# ETH10M100_RJ45wMAGNET.net
KiCad netlist of a schematic drawn in Altium Designer
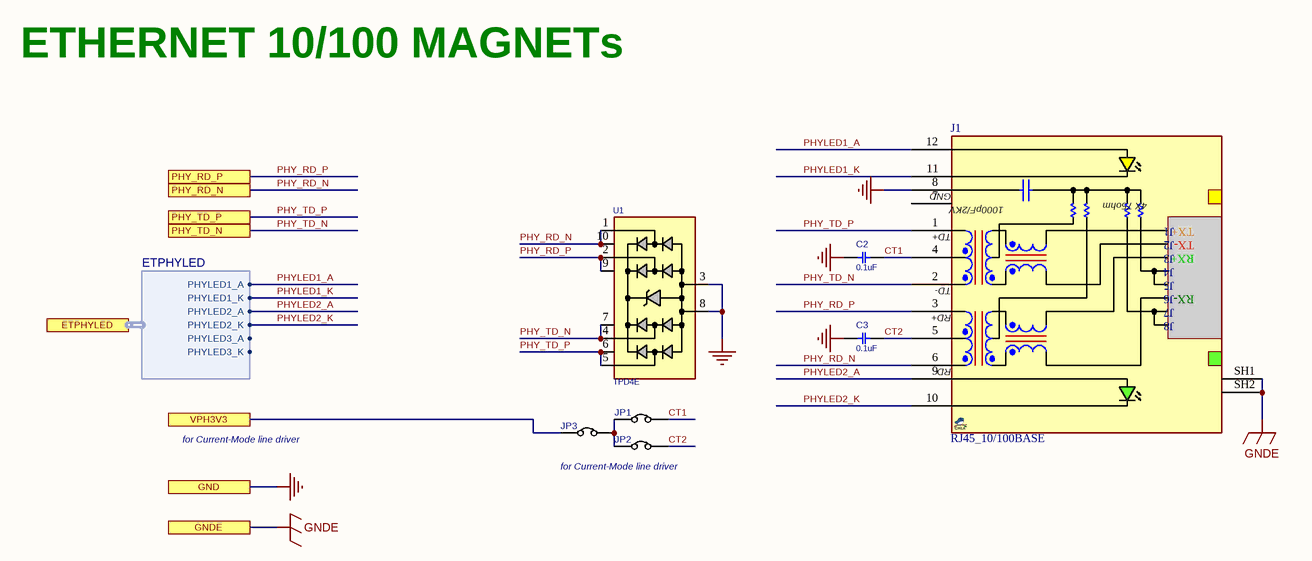
[diagram p0: ETH10M100_RJ45wMAGNET.SchDoc]

(export (version "E")
  (design (tool "Eeschema 10.0.6"))
  (components
    (comp (ref "C2")
      (value "0.1uF")
      (footprint "C0402")
      (description "CAP, MLCC")
      (libsource (lib "mlcc_smd_passive") (part "CAP_SMD_MLCC_22n50V"))
    )
    (comp (ref "C3")
      (value "0.1uF")
      (footprint "C0402")
      (description "CAP, MLCC")
      (libsource (lib "mlcc_smd_passive") (part "CAP_SMD_MLCC_22n50V"))
    )
    (comp (ref "J1")
      (value "RJ45_10/100BASE")
      (footprint "RJ45_8M_HR911105A")
      (description "RJ45, 10/100BASE, G/Y LED")
      (fields (field (name "MANF") "Hanrun") (field (name "MANF_P#") "HR911105A"))
      (libsource (lib "conn_rj_ModularJack") (part "RJ45_HR911105A"))
    )
    (comp (ref "JP1")
      (value "JMPSOLDER")
      (footprint "JP_30X50")
      (description "JUMPER, HEADER 2PIN")
      (fields (field (name "MANF") "MANF") (field (name "MANF_P#") "MANF_P#"))
      (libsource (lib "test-tp_jumper") (part "JUMPER_SOLDER"))
    )
    (comp (ref "JP2")
      (value "JMPSOLDER")
      (footprint "JP_30X50")
      (description "JUMPER, HEADER 2PIN")
      (fields (field (name "MANF") "MANF") (field (name "MANF_P#") "MANF_P#"))
      (libsource (lib "test-tp_jumper") (part "JUMPER_SOLDER"))
    )
    (comp (ref "JP3")
      (value "JMPSOLDER")
      (footprint "JP_30X50")
      (description "JUMPER, HEADER 2PIN")
      (fields (field (name "MANF") "MANF") (field (name "MANF_P#") "MANF_P#"))
      (libsource (lib "test-tp_jumper") (part "JUMPER_SOLDER"))
    )
    (comp (ref "U1")
      (value "TPD4E")
      (footprint "SON50_10_2510")
      (description "TVS, ESD PROTECT, 4CH,")
      (fields (field (name "MANF_P#") "TPD4E05U06DQA") (field (name "MANF") "Texas Instruments"))
      (libsource (lib "protect_tvs_esd_fuse") (part "TVS_X4_TPD4E05U06"))
    )
  )
  (nets
    (net (code "2") (name "/CT1") (class "Default")
      (node (ref "C2") (pin "2") (pinfunction "2_2") (pintype "passive"))
      (node (ref "J1") (pin "4") (pinfunction "TCT_4") (pintype "passive"))
      (node (ref "JP1") (pin "2") (pinfunction "2_2") (pintype "passive"))
    )
    (net (code "3") (name "/CT2") (class "Default")
      (node (ref "C3") (pin "2") (pinfunction "2_2") (pintype "passive"))
      (node (ref "J1") (pin "5") (pinfunction "RCT_5") (pintype "passive"))
      (node (ref "JP2") (pin "2") (pinfunction "2_2") (pintype "passive"))
    )
    (net (code "4") (name "/PHYLED1_A") (class "Default")
      (node (ref "J1") (pin "12") (pinfunction "YLED+_12") (pintype "passive"))
    )
    (net (code "5") (name "/PHYLED1_K") (class "Default")
      (node (ref "J1") (pin "11") (pinfunction "YLED-_11") (pintype "passive"))
    )
    (net (code "6") (name "/PHYLED2_A") (class "Default")
      (node (ref "J1") (pin "9") (pinfunction "GLED+_9") (pintype "passive"))
    )
    (net (code "7") (name "/PHYLED2_K") (class "Default")
      (node (ref "J1") (pin "10") (pinfunction "GLED-_10") (pintype "passive"))
    )
    (net (code "8") (name "/PHY_RD_N") (class "Default")
      (node (ref "J1") (pin "6") (pinfunction "RD-_6") (pintype "passive"))
      (node (ref "U1") (pin "1") (pinfunction "1_1") (pintype "passive"))
      (node (ref "U1") (pin "10") (pinfunction "10_10") (pintype "passive"))
    )
    (net (code "9") (name "/PHY_RD_P") (class "Default")
      (node (ref "J1") (pin "3") (pinfunction "RD+_3") (pintype "passive"))
      (node (ref "U1") (pin "2") (pinfunction "2_2") (pintype "passive"))
      (node (ref "U1") (pin "9") (pinfunction "9_9") (pintype "passive"))
    )
    (net (code "10") (name "/PHY_TD_N") (class "Default")
      (node (ref "J1") (pin "2") (pinfunction "TD-_2") (pintype "passive"))
      (node (ref "U1") (pin "4") (pinfunction "4_4") (pintype "passive"))
      (node (ref "U1") (pin "7") (pinfunction "7_7") (pintype "passive"))
    )
    (net (code "11") (name "/PHY_TD_P") (class "Default")
      (node (ref "J1") (pin "1") (pinfunction "TD+_1") (pintype "passive"))
      (node (ref "U1") (pin "5") (pinfunction "5_5") (pintype "passive"))
      (node (ref "U1") (pin "6") (pinfunction "6_6") (pintype "passive"))
    )
    (net (code "12") (name "/VPH3V3") (class "Default")
      (node (ref "JP3") (pin "1") (pinfunction "1_1") (pintype "passive"))
    )
    (net (code "14") (name "GND") (class "Default")
      (node (ref "C2") (pin "1") (pinfunction "1_1") (pintype "passive"))
      (node (ref "C3") (pin "1") (pinfunction "1_1") (pintype "passive"))
      (node (ref "J1") (pin "8") (pinfunction "CHSGND_8") (pintype "passive"))
      (node (ref "U1") (pin "3") (pinfunction "3_3") (pintype "passive"))
      (node (ref "U1") (pin "8") (pinfunction "8_8") (pintype "passive"))
    )
    (net (code "15") (name "GNDE") (class "Default")
      (node (ref "J1") (pin "SH1") (pinfunction "SH1_SH1") (pintype "passive"))
      (node (ref "J1") (pin "SH2") (pinfunction "SH2_SH2") (pintype "passive"))
    )
    (net (code "16") (name "Net-(JP1-Pad1)") (class "Default")
      (node (ref "JP1") (pin "1") (pinfunction "1_1") (pintype "passive"))
      (node (ref "JP2") (pin "1") (pinfunction "1_1") (pintype "passive"))
      (node (ref "JP3") (pin "2") (pinfunction "2_2") (pintype "passive"))
    )
    (net (code "17") (name "unconnected-(J1-NC-Pad7)") (class "Default")
      (node (ref "J1") (pin "7") (pinfunction "NC_7") (pintype "passive"))
    )
  )
)
